# RotaryEncoder_8Ch_Selectable.net
KiCad netlist of a schematic drawn in EAGLE
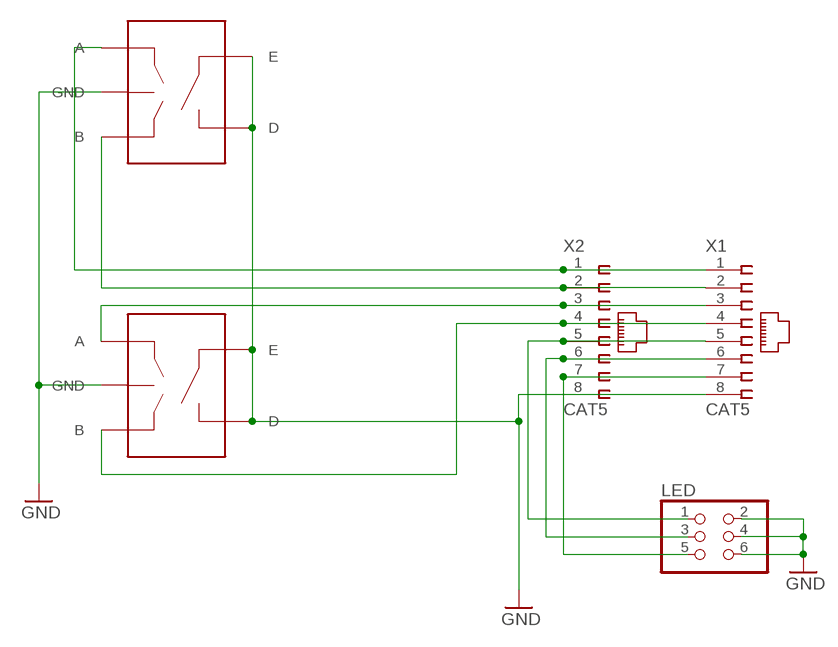
[diagram p0: schematic, sheet 1]

(export (version "E")
  (design (tool "Eeschema 10.0.6"))
  (components
    (comp (ref "ENC1")
      (value "PEC09")
      (footprint "eagle-import:PEC092320FS")
      (libsource (lib "eagle-import") (part "PEC09"))
    )
    (comp (ref "ENC2")
      (value "PEC09")
      (footprint "eagle-import:PEC092320FS")
      (libsource (lib "eagle-import") (part "PEC09"))
    )
    (comp (ref "LED")
      (value "PINHD-2X3")
      (footprint "eagle-import:2X03")
      (libsource (lib "eagle-import") (part "PINHD-2X3"))
    )
    (comp (ref "X1")
      (value "CAT5")
      (footprint "eagle-import:555164-1")
      (libsource (lib "eagle-import") (part "CAT5"))
    )
    (comp (ref "X2")
      (value "CAT5")
      (footprint "eagle-import:555164-1")
      (libsource (lib "eagle-import") (part "CAT5"))
    )
  )
  (nets
    (net (code "1") (name "GND") (class "Default")
      (node (ref "ENC1") (pin "C") (pinfunction "GND_C") (pintype "bidirectional"))
      (node (ref "ENC1") (pin "D") (pinfunction "D_D") (pintype "bidirectional"))
      (node (ref "ENC1") (pin "E") (pinfunction "E_E") (pintype "bidirectional"))
      (node (ref "ENC2") (pin "C") (pinfunction "GND_C") (pintype "bidirectional"))
      (node (ref "ENC2") (pin "D") (pinfunction "D_D") (pintype "bidirectional"))
      (node (ref "ENC2") (pin "E") (pinfunction "E_E") (pintype "bidirectional"))
      (node (ref "LED") (pin "2") (pinfunction "2_2") (pintype "passive"))
      (node (ref "LED") (pin "4") (pinfunction "4_4") (pintype "passive"))
      (node (ref "LED") (pin "6") (pinfunction "6_6") (pintype "passive"))
      (node (ref "X1") (pin "8") (pinfunction "8_8") (pintype "passive"))
      (node (ref "X2") (pin "8") (pinfunction "8_8") (pintype "passive"))
    )
    (net (code "2") (name "Net-(ENC1-PadA)") (class "Default")
      (node (ref "ENC1") (pin "A") (pinfunction "A_A") (pintype "bidirectional"))
      (node (ref "X1") (pin "1") (pinfunction "1_1") (pintype "passive"))
      (node (ref "X2") (pin "1") (pinfunction "1_1") (pintype "passive"))
    )
    (net (code "3") (name "Net-(ENC1-PadB)") (class "Default")
      (node (ref "ENC1") (pin "B") (pinfunction "B_B") (pintype "bidirectional"))
      (node (ref "X1") (pin "2") (pinfunction "2_2") (pintype "passive"))
      (node (ref "X2") (pin "2") (pinfunction "2_2") (pintype "passive"))
    )
    (net (code "4") (name "Net-(ENC2-PadA)") (class "Default")
      (node (ref "ENC2") (pin "A") (pinfunction "A_A") (pintype "bidirectional"))
      (node (ref "X1") (pin "3") (pinfunction "3_3") (pintype "passive"))
      (node (ref "X2") (pin "3") (pinfunction "3_3") (pintype "passive"))
    )
    (net (code "5") (name "Net-(ENC2-PadB)") (class "Default")
      (node (ref "ENC2") (pin "B") (pinfunction "B_B") (pintype "bidirectional"))
      (node (ref "X1") (pin "4") (pinfunction "4_4") (pintype "passive"))
      (node (ref "X2") (pin "4") (pinfunction "4_4") (pintype "passive"))
    )
    (net (code "6") (name "Net-(LED-Pad1)") (class "Default")
      (node (ref "LED") (pin "1") (pinfunction "1_1") (pintype "passive"))
      (node (ref "X1") (pin "5") (pinfunction "5_5") (pintype "passive"))
      (node (ref "X2") (pin "5") (pinfunction "5_5") (pintype "passive"))
    )
    (net (code "7") (name "Net-(LED-Pad3)") (class "Default")
      (node (ref "LED") (pin "3") (pinfunction "3_3") (pintype "passive"))
      (node (ref "X1") (pin "6") (pinfunction "6_6") (pintype "passive"))
      (node (ref "X2") (pin "6") (pinfunction "6_6") (pintype "passive"))
    )
    (net (code "8") (name "Net-(LED-Pad5)") (class "Default")
      (node (ref "LED") (pin "5") (pinfunction "5_5") (pintype "passive"))
      (node (ref "X1") (pin "7") (pinfunction "7_7") (pintype "passive"))
      (node (ref "X2") (pin "7") (pinfunction "7_7") (pintype "passive"))
    )
  )
)
